# EVK-NORA-W4_SCHEM_0003_USBhub_FTDI.net
KiCad netlist of a schematic drawn in Altium Designer
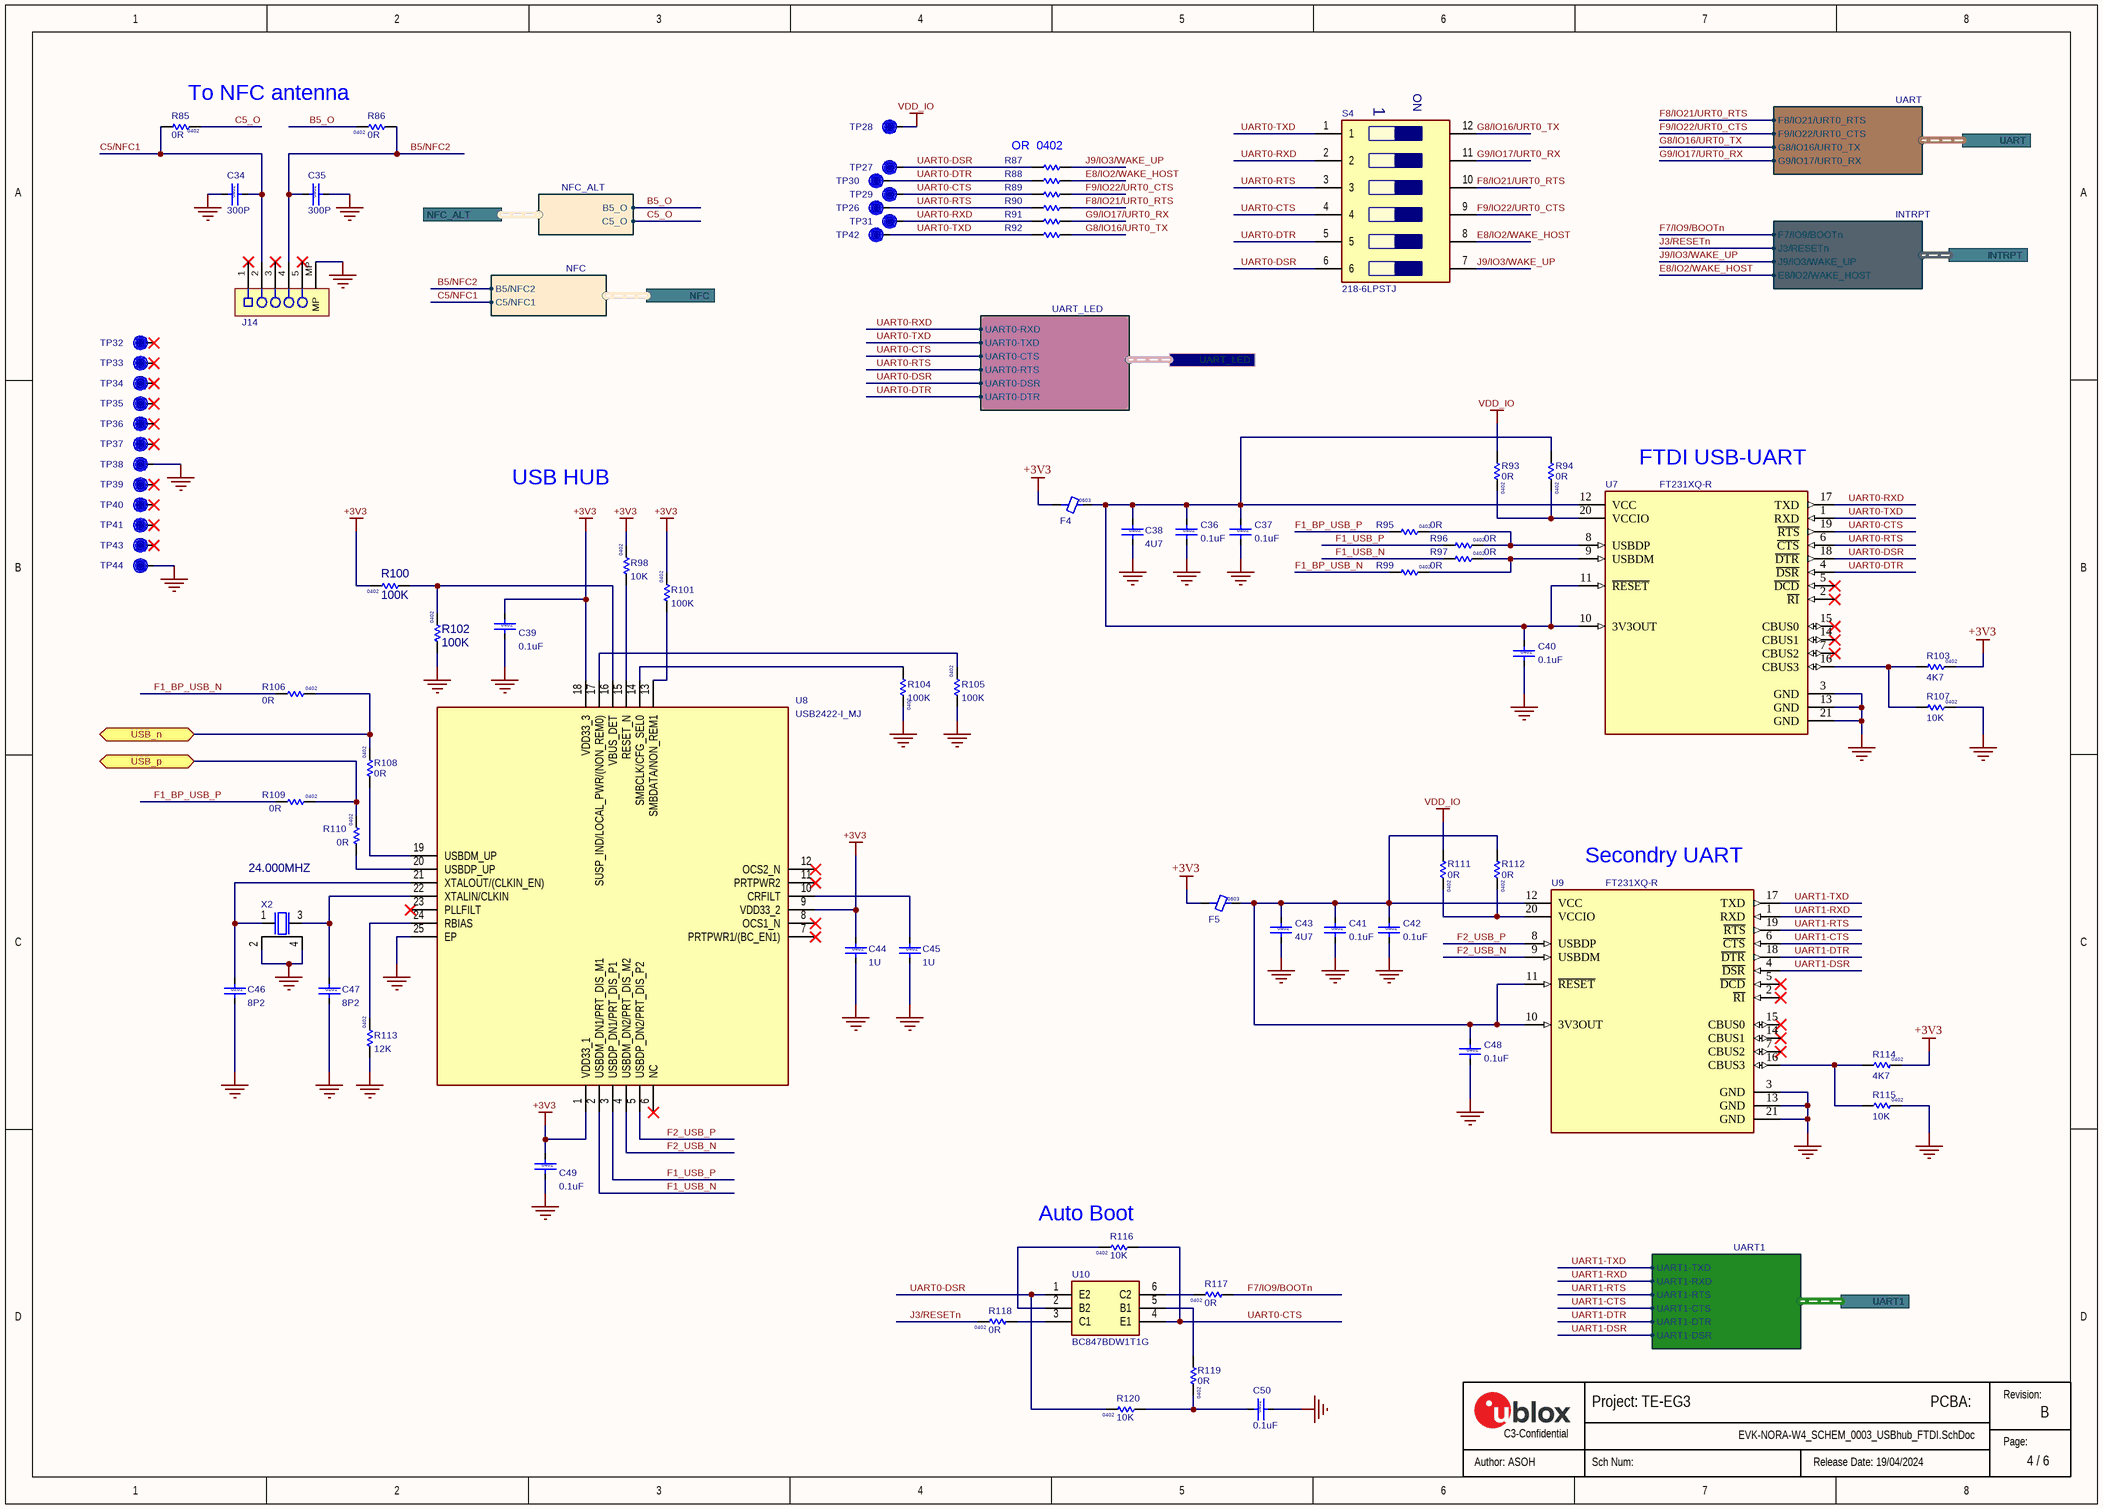
[diagram p0: EVK-NORA-W4_SCHEM_0003_USBhub_FTDI.SchDoc]

(export (version "E")
  (design (tool "Eeschema 10.0.6"))
  (components
    (comp (ref "C34")
      (value "300P")
      (footprint "Cap 0402 HD")
      (description "CAP CER C0G 0402 300P 50V")
      (fields
        (field (name "SIZE") "0402")
        (field (name "PART NUMBER") "UBXH01-0000594")
        (field (name "MANUFACTURER") "Murata Manufacturing Company, Ltd.")
        (field (name "EDITOR") "eric.moog")
      )
      (libsource (lib "UBX_Parts_DB_Lib") (part "Cap Chip"))
    )
    (comp (ref "C35")
      (value "300P")
      (footprint "Cap 0402 HD")
      (description "CAP CER C0G 0402 300P 50V")
      (fields
        (field (name "SIZE") "0402")
        (field (name "PART NUMBER") "UBXH01-0000594")
        (field (name "MANUFACTURER") "Murata Manufacturing Company, Ltd.")
        (field (name "EDITOR") "eric.moog")
      )
      (libsource (lib "UBX_Parts_DB_Lib") (part "Cap Chip"))
    )
    (comp (ref "C36")
      (value "0.1uF")
      (footprint "Cap 0402 HD")
      (description "Cap, Ceramic 0.1uF 10V 10% X5R 0402")
      (fields
        (field (name "SIZE") "0402")
        (field (name "PART NUMBER") "120-00016")
        (field (name "MANUFACTURER") "Murata Electronics North America")
      )
      (libsource (lib "Arena_Parts_DB_Lib") (part "Cap Chip"))
    )
    (comp (ref "C37")
      (value "0.1uF")
      (footprint "Cap 0402 HD")
      (description "Cap, Ceramic 0.1uF 10V 10% X5R 0402")
      (fields
        (field (name "SIZE") "0402")
        (field (name "PART NUMBER") "120-00016")
        (field (name "MANUFACTURER") "Murata Electronics North America")
      )
      (libsource (lib "Arena_Parts_DB_Lib") (part "Cap Chip"))
    )
    (comp (ref "C38")
      (value "4U7")
      (footprint "Cap 0402 HD")
      (description "CAP CER X5R 0402 4U7 20% 10V")
      (fields
        (field (name "SIZE") "0402")
        (field (name "PART NUMBER") "UBXH01-0000243")
        (field (name "TOLERANCE") "20%")
        (field (name "EDITOR") "martin.pilik")
        (field (name "RELEASED BY") "fabrice.bret-dibat")
      )
      (libsource (lib "UBX_Parts_DB_Lib") (part "Cap Chip"))
    )
    (comp (ref "C39")
      (value "0.1uF")
      (footprint "Cap 0402 HD")
      (description "Cap, Ceramic 0.1uF 10V 10% X5R 0402")
      (fields
        (field (name "SIZE") "0402")
        (field (name "PART NUMBER") "120-00016")
        (field (name "MANUFACTURER") "Murata Electronics North America")
      )
      (libsource (lib "Arena_Parts_DB_Lib") (part "Cap Chip"))
    )
    (comp (ref "C40")
      (value "0.1uF")
      (footprint "Cap 0402 HD")
      (description "Cap, Ceramic 0.1uF 10V 10% X5R 0402")
      (fields
        (field (name "SIZE") "0402")
        (field (name "PART NUMBER") "120-00016")
        (field (name "MANUFACTURER") "Murata Electronics North America")
      )
      (libsource (lib "Arena_Parts_DB_Lib") (part "Cap Chip"))
    )
    (comp (ref "C41")
      (value "0.1uF")
      (footprint "Cap 0402 HD")
      (description "Cap, Ceramic 0.1uF 10V 10% X5R 0402")
      (fields
        (field (name "SIZE") "0402")
        (field (name "PART NUMBER") "120-00016")
        (field (name "MANUFACTURER") "Murata Electronics North America")
      )
      (libsource (lib "Arena_Parts_DB_Lib") (part "Cap Chip"))
    )
    (comp (ref "C42")
      (value "0.1uF")
      (footprint "Cap 0402 HD")
      (description "Cap, Ceramic 0.1uF 10V 10% X5R 0402")
      (fields
        (field (name "SIZE") "0402")
        (field (name "PART NUMBER") "120-00016")
        (field (name "MANUFACTURER") "Murata Electronics North America")
      )
      (libsource (lib "Arena_Parts_DB_Lib") (part "Cap Chip"))
    )
    (comp (ref "C43")
      (value "4U7")
      (footprint "Cap 0402 HD")
      (description "CAP CER X5R 0402 4U7 20% 10V")
      (fields
        (field (name "SIZE") "0402")
        (field (name "PART NUMBER") "UBXH01-0000243")
        (field (name "TOLERANCE") "20%")
        (field (name "EDITOR") "martin.pilik")
        (field (name "RELEASED BY") "fabrice.bret-dibat")
      )
      (libsource (lib "UBX_Parts_DB_Lib") (part "Cap Chip"))
    )
    (comp (ref "C44")
      (value "1U")
      (footprint "Cap 0402 HD")
      (description "CAP CER X5R 0402 1U 10% 10V")
      (fields
        (field (name "SIZE") "0402")
        (field (name "PART NUMBER") "UBXH01-0000248")
        (field (name "TOLERANCE") "10%")
        (field (name "EDITOR") "michael.hein")
        (field (name "RELEASED BY") "igor.shevchenko")
      )
      (libsource (lib "UBX_Parts_DB_Lib") (part "Cap Chip"))
    )
    (comp (ref "C45")
      (value "1U")
      (footprint "Cap 0402 HD")
      (description "CAP CER X5R 0402 1U 10% 10V")
      (fields
        (field (name "SIZE") "0402")
        (field (name "PART NUMBER") "UBXH01-0000248")
        (field (name "TOLERANCE") "10%")
        (field (name "EDITOR") "michael.hein")
        (field (name "RELEASED BY") "igor.shevchenko")
      )
      (libsource (lib "UBX_Parts_DB_Lib") (part "Cap Chip"))
    )
    (comp (ref "C46")
      (value "8P2")
      (footprint "Cap 0201 HD")
      (description "CAP CER C0G 0201 8P2 +/-0.5P 25V")
      (fields
        (field (name "SIZE") "0201")
        (field (name "PART NUMBER") "UBXH01-0013002")
        (field (name "TOLERANCE") "+/-0.5P")
        (field (name "EDITOR") "roland.rust")
        (field (name "RELEASED BY") "roland.rust")
      )
      (libsource (lib "UBX_Parts_DB_Lib") (part "Cap Chip"))
    )
    (comp (ref "C47")
      (value "8P2")
      (footprint "Cap 0201 HD")
      (description "CAP CER C0G 0201 8P2 +/-0.5P 25V")
      (fields
        (field (name "SIZE") "0201")
        (field (name "PART NUMBER") "UBXH01-0013002")
        (field (name "TOLERANCE") "+/-0.5P")
        (field (name "EDITOR") "roland.rust")
        (field (name "RELEASED BY") "roland.rust")
      )
      (libsource (lib "UBX_Parts_DB_Lib") (part "Cap Chip"))
    )
    (comp (ref "C48")
      (value "0.1uF")
      (footprint "Cap 0402 HD")
      (description "Cap, Ceramic 0.1uF 10V 10% X5R 0402")
      (fields
        (field (name "SIZE") "0402")
        (field (name "PART NUMBER") "120-00016")
        (field (name "MANUFACTURER") "Murata Electronics North America")
      )
      (libsource (lib "Arena_Parts_DB_Lib") (part "Cap Chip"))
    )
    (comp (ref "C49")
      (value "0.1uF")
      (footprint "Cap 0402 HD")
      (description "Cap, Ceramic 0.1uF 10V 10% X5R 0402")
      (fields
        (field (name "SIZE") "0402")
        (field (name "PART NUMBER") "120-00016")
        (field (name "MANUFACTURER") "Murata Electronics North America")
      )
      (libsource (lib "Arena_Parts_DB_Lib") (part "Cap Chip"))
    )
    (comp (ref "C50")
      (value "0.1uF")
      (footprint "Cap 0402 HD")
      (description "Cap, Ceramic 0.1uF 10V 10% X5R 0402")
      (fields
        (field (name "SIZE") "0402")
        (field (name "PART NUMBER") "120-00016")
        (field (name "MANUFACTURER") "Murata Electronics North America")
      )
      (libsource (lib "Arena_Parts_DB_Lib") (part "Cap Chip"))
    )
    (comp (ref "F4")
      (value "UBXH08-0000001")
      (footprint "IND_0603_1750Lx950Wx1050H_600x800Pad_800G_FLX")
      (description "FERRITE BEAD 0603 600 OHM AT 100MHZ 600OHM 500mA")
      (fields
        (field (name "SIZE") "0603")
        (field (name "MANUFACTURER") "TDK Corporation")
        (field (name "EDITOR") "daniel.hurni")
        (field (name "RELEASED BY") "martin.frauchiger")
      )
      (libsource (lib "UBX_Parts_DB_Lib") (part "FB sm"))
    )
    (comp (ref "F5")
      (value "UBXH08-0000001")
      (footprint "IND_0603_1750Lx950Wx1050H_600x800Pad_800G_FLX")
      (description "FERRITE BEAD 0603 600 OHM AT 100MHZ 600OHM 500mA")
      (fields
        (field (name "SIZE") "0603")
        (field (name "MANUFACTURER") "TDK Corporation")
        (field (name "EDITOR") "daniel.hurni")
        (field (name "RELEASED BY") "martin.frauchiger")
      )
      (libsource (lib "UBX_Parts_DB_Lib") (part "FB sm"))
    )
    (comp (ref "J14")
      (value "UBXH04-0000798")
      (footprint "AVX/Kyocera - 046284005001846")
      (description "0.50MM PITCH SMD RA FFC FPC CONN 5 -PIN 50V 400mA")
      (fields
        (field (name "VOLTAGE") "50V")
        (field (name "MANUFACTURER") "AVX")
        (field (name "EDITOR") "eric.moog")
      )
      (libsource (lib "UBX_Parts_DB_Lib") (part "CON-5Pin_1Row-046284005001846"))
    )
    (comp (ref "R85")
      (value "0R")
      (footprint "RES 0402 HD")
      (description "RES THICK FILM CHIP 0402 0R 0 100mW")
      (fields
        (field (name "SIZE") "0402")
        (field (name "PART NUMBER") "UBXH18-0003002")
        (field (name "TOLERANCE") "0")
        (field (name "EDITOR") "charlotte.biber")
        (field (name "RELEASED BY") "peter.mueller")
      )
      (libsource (lib "UBX_Parts_DB_Lib") (part "Res sm"))
    )
    (comp (ref "R86")
      (value "0R")
      (footprint "RES 0402 HD")
      (description "RES THICK FILM CHIP 0402 0R 0 100mW")
      (fields
        (field (name "SIZE") "0402")
        (field (name "PART NUMBER") "UBXH18-0003002")
        (field (name "TOLERANCE") "0")
        (field (name "EDITOR") "charlotte.biber")
        (field (name "RELEASED BY") "peter.mueller")
      )
      (libsource (lib "UBX_Parts_DB_Lib") (part "Res sm"))
    )
    (comp (ref "R87")
      (value "UBXH18-00030020R")
      (footprint "RES 0402 HD")
      (description "RES THICK FILM CHIP 0402 0R 0 100mW")
      (fields
        (field (name "PART NUMBER") "UBXH18-0003002")
        (field (name "TOLERANCE") "0")
        (field (name "EDITOR") "charlotte.biber")
        (field (name "RELEASED BY") "peter.mueller")
      )
      (libsource (lib "UBX_Parts_DB_Lib") (part "Res sm"))
    )
    (comp (ref "R88")
      (value "UBXH18-00030020R")
      (footprint "RES 0402 HD")
      (description "RES THICK FILM CHIP 0402 0R 0 100mW")
      (fields
        (field (name "PART NUMBER") "UBXH18-0003002")
        (field (name "TOLERANCE") "0")
        (field (name "EDITOR") "charlotte.biber")
        (field (name "RELEASED BY") "peter.mueller")
      )
      (libsource (lib "UBX_Parts_DB_Lib") (part "Res sm"))
    )
    (comp (ref "R89")
      (value "UBXH18-00030020R")
      (footprint "RES 0402 HD")
      (description "RES THICK FILM CHIP 0402 0R 0 100mW")
      (fields
        (field (name "PART NUMBER") "UBXH18-0003002")
        (field (name "TOLERANCE") "0")
        (field (name "EDITOR") "charlotte.biber")
        (field (name "RELEASED BY") "peter.mueller")
      )
      (libsource (lib "UBX_Parts_DB_Lib") (part "Res sm"))
    )
    (comp (ref "R90")
      (value "UBXH18-00030020R")
      (footprint "RES 0402 HD")
      (description "RES THICK FILM CHIP 0402 0R 0 100mW")
      (fields
        (field (name "PART NUMBER") "UBXH18-0003002")
        (field (name "TOLERANCE") "0")
        (field (name "EDITOR") "charlotte.biber")
        (field (name "RELEASED BY") "peter.mueller")
      )
      (libsource (lib "UBX_Parts_DB_Lib") (part "Res sm"))
    )
    (comp (ref "R91")
      (value "UBXH18-00030020R")
      (footprint "RES 0402 HD")
      (description "RES THICK FILM CHIP 0402 0R 0 100mW")
      (fields
        (field (name "PART NUMBER") "UBXH18-0003002")
        (field (name "TOLERANCE") "0")
        (field (name "EDITOR") "charlotte.biber")
        (field (name "RELEASED BY") "peter.mueller")
      )
      (libsource (lib "UBX_Parts_DB_Lib") (part "Res sm"))
    )
    (comp (ref "R92")
      (value "UBXH18-00030020R")
      (footprint "RES 0402 HD")
      (description "RES THICK FILM CHIP 0402 0R 0 100mW")
      (fields
        (field (name "PART NUMBER") "UBXH18-0003002")
        (field (name "TOLERANCE") "0")
        (field (name "EDITOR") "charlotte.biber")
        (field (name "RELEASED BY") "peter.mueller")
      )
      (libsource (lib "UBX_Parts_DB_Lib") (part "Res sm"))
    )
    (comp (ref "R93")
      (value "0R")
      (footprint "RES 0402 HD")
      (description "RES THICK FILM CHIP 0402 0R 0 100mW")
      (fields
        (field (name "SIZE") "0402")
        (field (name "PART NUMBER") "UBXH18-0003002")
        (field (name "TOLERANCE") "0")
        (field (name "EDITOR") "charlotte.biber")
        (field (name "RELEASED BY") "peter.mueller")
      )
      (libsource (lib "UBX_Parts_DB_Lib") (part "Res sm"))
    )
    (comp (ref "R94")
      (value "0R")
      (footprint "RES 0402 HD")
      (description "RES THICK FILM CHIP 0402 0R 0 100mW")
      (fields
        (field (name "SIZE") "0402")
        (field (name "PART NUMBER") "UBXH18-0003002")
        (field (name "TOLERANCE") "0")
        (field (name "EDITOR") "charlotte.biber")
        (field (name "RELEASED BY") "peter.mueller")
      )
      (libsource (lib "UBX_Parts_DB_Lib") (part "Res sm"))
    )
    (comp (ref "R95")
      (value "0R")
      (footprint "RES 0402 HD")
      (description "RES THICK FILM CHIP 0402 0R 0 100mW")
      (fields
        (field (name "SIZE") "0402")
        (field (name "PART NUMBER") "UBXH18-0003002")
        (field (name "TOLERANCE") "0")
        (field (name "EDITOR") "charlotte.biber")
        (field (name "RELEASED BY") "peter.mueller")
      )
      (libsource (lib "UBX_Parts_DB_Lib") (part "Res sm"))
    )
    (comp (ref "R96")
      (value "0R")
      (footprint "RES 0402 HD")
      (description "RES THICK FILM CHIP 0402 0R 0 100mW")
      (fields
        (field (name "SIZE") "0402")
        (field (name "PART NUMBER") "UBXH18-0003002")
        (field (name "TOLERANCE") "0")
        (field (name "EDITOR") "charlotte.biber")
        (field (name "RELEASED BY") "peter.mueller")
      )
      (libsource (lib "UBX_Parts_DB_Lib") (part "Res sm"))
    )
    (comp (ref "R97")
      (value "0R")
      (footprint "RES 0402 HD")
      (description "RES THICK FILM CHIP 0402 0R 0 100mW")
      (fields
        (field (name "SIZE") "0402")
        (field (name "PART NUMBER") "UBXH18-0003002")
        (field (name "TOLERANCE") "0")
        (field (name "EDITOR") "charlotte.biber")
        (field (name "RELEASED BY") "peter.mueller")
      )
      (libsource (lib "UBX_Parts_DB_Lib") (part "Res sm"))
    )
    (comp (ref "R98")
      (value "10K")
      (footprint "RES 0402 HD")
      (description "RES THICK FILM CHIP 0402 10K 1% 63mW")
      (fields
        (field (name "SIZE") "0402")
        (field (name "PART NUMBER") "UBXH18-0000065")
        (field (name "TOLERANCE") "1%")
        (field (name "EDITOR") "erian.bezhani")
        (field (name "RELEASED BY") "massimo.vlacci")
      )
      (libsource (lib "UBX_Parts_DB_Lib") (part "Res sm"))
    )
    (comp (ref "R99")
      (value "0R")
      (footprint "RES 0402 HD")
      (description "RES THICK FILM CHIP 0402 0R 0 100mW")
      (fields
        (field (name "SIZE") "0402")
        (field (name "PART NUMBER") "UBXH18-0003002")
        (field (name "TOLERANCE") "0")
        (field (name "EDITOR") "charlotte.biber")
        (field (name "RELEASED BY") "peter.mueller")
      )
      (libsource (lib "UBX_Parts_DB_Lib") (part "Res sm"))
    )
    (comp (ref "R100")
      (value "100K")
      (footprint "RES 0402 HD")
      (description "RES THICK FILM CHIP 0402 100K 1% 63mW")
      (fields
        (field (name "SIZE") "0402")
        (field (name "PART NUMBER") "UBXH18-0000005")
        (field (name "TOLERANCE") "1%")
        (field (name "EDITOR") "dario.antonaz")
        (field (name "RELEASED BY") "sandro.sestan")
      )
      (libsource (lib "UBX_Parts_DB_Lib") (part "Res sm"))
    )
    (comp (ref "R101")
      (value "100K")
      (footprint "RES 0402 HD")
      (description "RES THICK FILM CHIP 0402 100K 1% 63mW")
      (fields
        (field (name "SIZE") "0402")
        (field (name "PART NUMBER") "UBXH18-0000005")
        (field (name "TOLERANCE") "1%")
        (field (name "EDITOR") "dario.antonaz")
        (field (name "RELEASED BY") "sandro.sestan")
      )
      (libsource (lib "UBX_Parts_DB_Lib") (part "Res sm"))
    )
    (comp (ref "R102")
      (value "100K")
      (footprint "RES 0402 HD")
      (description "RES THICK FILM CHIP 0402 100K 1% 63mW")
      (fields
        (field (name "SIZE") "0402")
        (field (name "PART NUMBER") "UBXH18-0000005")
        (field (name "TOLERANCE") "1%")
        (field (name "EDITOR") "dario.antonaz")
        (field (name "RELEASED BY") "sandro.sestan")
      )
      (libsource (lib "UBX_Parts_DB_Lib") (part "Res sm"))
    )
    (comp (ref "R103")
      (value "4K7")
      (footprint "RES_0402_1100Lx600Wx400H_500x600Pad_400G_FLX")
      (description "RES THICK FILM CHIP 0402 4K7 5% 100mW")
      (fields
        (field (name "SIZE") "0402")
        (field (name "PART NUMBER") "UBXH18-0008065")
        (field (name "TOLERANCE") "5%")
        (field (name "EDITOR") "martin.frauchiger")
        (field (name "RELEASED BY") "martin.frauchiger")
      )
      (libsource (lib "UBX_Parts_DB_Lib") (part "Res sm"))
    )
    (comp (ref "R104")
      (value "100K")
      (footprint "RES 0402 HD")
      (description "RES THICK FILM CHIP 0402 100K 1% 63mW")
      (fields
        (field (name "SIZE") "0402")
        (field (name "PART NUMBER") "UBXH18-0000005")
        (field (name "TOLERANCE") "1%")
        (field (name "EDITOR") "dario.antonaz")
        (field (name "RELEASED BY") "sandro.sestan")
      )
      (libsource (lib "UBX_Parts_DB_Lib") (part "Res sm"))
    )
    (comp (ref "R105")
      (value "100K")
      (footprint "RES 0402 HD")
      (description "RES THICK FILM CHIP 0402 100K 1% 63mW")
      (fields
        (field (name "SIZE") "0402")
        (field (name "PART NUMBER") "UBXH18-0000005")
        (field (name "TOLERANCE") "1%")
        (field (name "EDITOR") "dario.antonaz")
        (field (name "RELEASED BY") "sandro.sestan")
      )
      (libsource (lib "UBX_Parts_DB_Lib") (part "Res sm"))
    )
    (comp (ref "R106")
      (value "0R")
      (footprint "RES 0402 HD")
      (description "RES THICK FILM CHIP 0402 0R 0 100mW")
      (fields
        (field (name "SIZE") "0402")
        (field (name "PART NUMBER") "UBXH18-0003002")
        (field (name "TOLERANCE") "0")
        (field (name "EDITOR") "charlotte.biber")
        (field (name "RELEASED BY") "peter.mueller")
      )
      (libsource (lib "UBX_Parts_DB_Lib") (part "Res sm"))
    )
    (comp (ref "R107")
      (value "10K")
      (footprint "RES_0402_1100Lx600Wx400H_500x600Pad_400G_FLX")
      (description "RES THICK FILM CHIP 0402 10K 5% 100mW")
      (fields
        (field (name "SIZE") "0402")
        (field (name "PART NUMBER") "UBXH18-0008073")
        (field (name "TOLERANCE") "5%")
        (field (name "EDITOR") "martin.frauchiger")
        (field (name "RELEASED BY") "martin.frauchiger")
      )
      (libsource (lib "UBX_Parts_DB_Lib") (part "Res sm"))
    )
    (comp (ref "R108")
      (value "0R")
      (footprint "RES 0402 HD")
      (description "RES THICK FILM CHIP 0402 0R 0 100mW")
      (fields
        (field (name "SIZE") "0402")
        (field (name "PART NUMBER") "UBXH18-0003002")
        (field (name "TOLERANCE") "0")
        (field (name "EDITOR") "charlotte.biber")
        (field (name "RELEASED BY") "peter.mueller")
      )
      (libsource (lib "UBX_Parts_DB_Lib") (part "Res sm"))
    )
    (comp (ref "R109")
      (value "0R")
      (footprint "RES 0402 HD")
      (description "RES THICK FILM CHIP 0402 0R 0 100mW")
      (fields
        (field (name "SIZE") "0402")
        (field (name "PART NUMBER") "UBXH18-0003002")
        (field (name "TOLERANCE") "0")
        (field (name "EDITOR") "charlotte.biber")
        (field (name "RELEASED BY") "peter.mueller")
      )
      (libsource (lib "UBX_Parts_DB_Lib") (part "Res sm"))
    )
    (comp (ref "R110")
      (value "0R")
      (footprint "RES 0402 HD")
      (description "RES THICK FILM CHIP 0402 0R 0 100mW")
      (fields
        (field (name "SIZE") "0402")
        (field (name "PART NUMBER") "UBXH18-0003002")
        (field (name "TOLERANCE") "0")
        (field (name "EDITOR") "charlotte.biber")
        (field (name "RELEASED BY") "peter.mueller")
      )
      (libsource (lib "UBX_Parts_DB_Lib") (part "Res sm"))
    )
    (comp (ref "R111")
      (value "0R")
      (footprint "RES 0402 HD")
      (description "RES THICK FILM CHIP 0402 0R 0 100mW")
      (fields
        (field (name "SIZE") "0402")
        (field (name "PART NUMBER") "UBXH18-0003002")
        (field (name "TOLERANCE") "0")
        (field (name "EDITOR") "charlotte.biber")
        (field (name "RELEASED BY") "peter.mueller")
      )
      (libsource (lib "UBX_Parts_DB_Lib") (part "Res sm"))
    )
    (comp (ref "R112")
      (value "0R")
      (footprint "RES 0402 HD")
      (description "RES THICK FILM CHIP 0402 0R 0 100mW")
      (fields
        (field (name "SIZE") "0402")
        (field (name "PART NUMBER") "UBXH18-0003002")
        (field (name "TOLERANCE") "0")
        (field (name "EDITOR") "charlotte.biber")
        (field (name "RELEASED BY") "peter.mueller")
      )
      (libsource (lib "UBX_Parts_DB_Lib") (part "Res sm"))
    )
    (comp (ref "R113")
      (value "12K")
      (footprint "RES_0402_1100Lx600Wx400H_500x600Pad_400G_FLX")
      (description "RES THICK FILM CHIP 0402 12K 1% 62.5mW")
      (fields
        (field (name "SIZE") "0402")
        (field (name "PART NUMBER") "UBXH18-0000133")
        (field (name "TOLERANCE") "1%")
        (field (name "EDITOR") "pierpaolo.arban")
        (field (name "RELEASED BY") "dario.antonaz")
      )
      (libsource (lib "UBX_Parts_DB_Lib") (part "Res sm"))
    )
    (comp (ref "R114")
      (value "4K7")
      (footprint "RES_0402_1100Lx600Wx400H_500x600Pad_400G_FLX")
      (description "RES THICK FILM CHIP 0402 4K7 5% 100mW")
      (fields
        (field (name "SIZE") "0402")
        (field (name "PART NUMBER") "UBXH18-0008065")
        (field (name "TOLERANCE") "5%")
        (field (name "EDITOR") "martin.frauchiger")
        (field (name "RELEASED BY") "martin.frauchiger")
      )
      (libsource (lib "UBX_Parts_DB_Lib") (part "Res sm"))
    )
    (comp (ref "R115")
      (value "10K")
      (footprint "RES_0402_1100Lx600Wx400H_500x600Pad_400G_FLX")
      (description "RES THICK FILM CHIP 0402 10K 5% 100mW")
      (fields
        (field (name "SIZE") "0402")
        (field (name "PART NUMBER") "UBXH18-0008073")
        (field (name "TOLERANCE") "5%")
        (field (name "EDITOR") "martin.frauchiger")
        (field (name "RELEASED BY") "martin.frauchiger")
      )
      (libsource (lib "UBX_Parts_DB_Lib") (part "Res sm"))
    )
    (comp (ref "R116")
      (value "10K")
      (footprint "RES 0402 HD")
      (description "RES THICK FILM CHIP 0402 10K 1% 63mW")
      (fields
        (field (name "SIZE") "0402")
        (field (name "PART NUMBER") "UBXH18-0000065")
        (field (name "TOLERANCE") "1%")
        (field (name "EDITOR") "erian.bezhani")
        (field (name "RELEASED BY") "massimo.vlacci")
      )
      (libsource (lib "UBX_Parts_DB_Lib") (part "Res sm"))
    )
    (comp (ref "R117")
      (value "0R")
      (footprint "RES 0402 HD")
      (description "RES THICK FILM CHIP 0402 0R 0 100mW")
      (fields
        (field (name "SIZE") "0402")
        (field (name "PART NUMBER") "UBXH18-0003002")
        (field (name "TOLERANCE") "0")
        (field (name "EDITOR") "charlotte.biber")
        (field (name "RELEASED BY") "peter.mueller")
      )
      (libsource (lib "UBX_Parts_DB_Lib") (part "Res sm"))
    )
    (comp (ref "R118")
      (value "0R")
      (footprint "RES 0402 HD")
      (description "RES THICK FILM CHIP 0402 0R 0 100mW")
      (fields
        (field (name "SIZE") "0402")
        (field (name "PART NUMBER") "UBXH18-0003002")
        (field (name "TOLERANCE") "0")
        (field (name "EDITOR") "charlotte.biber")
        (field (name "RELEASED BY") "peter.mueller")
      )
      (libsource (lib "UBX_Parts_DB_Lib") (part "Res sm"))
    )
    (comp (ref "R119")
      (value "0R")
      (footprint "RES 0402 HD")
      (description "RES THICK FILM CHIP 0402 0R 0 100mW")
      (fields
        (field (name "SIZE") "0402")
        (field (name "PART NUMBER") "UBXH18-0003002")
        (field (name "TOLERANCE") "0")
        (field (name "EDITOR") "charlotte.biber")
        (field (name "RELEASED BY") "peter.mueller")
      )
      (libsource (lib "UBX_Parts_DB_Lib") (part "Res sm"))
    )
    (comp (ref "R120")
      (value "10K")
      (footprint "RES 0402 HD")
      (description "RES THICK FILM CHIP 0402 10K 1% 63mW")
      (fields
        (field (name "SIZE") "0402")
        (field (name "PART NUMBER") "UBXH18-0000065")
        (field (name "TOLERANCE") "1%")
        (field (name "EDITOR") "erian.bezhani")
        (field (name "RELEASED BY") "massimo.vlacci")
      )
      (libsource (lib "UBX_Parts_DB_Lib") (part "Res sm"))
    )
    (comp (ref "S4")
      (value "218-6LPSTJ")
      (footprint "SamacSys:2186LPSTJ")
      (description "Switch")
      (fields (field (name "MOUSER PART NUMBER") "774-2186LPSTJ"))
      (libsource (lib "SamacSys") (part "218-6LPSTJ"))
    )
    (comp (ref "TP26")
      (value "TP")
      (footprint "TP10R")
      (description "Testpoint, Round 1.0mm Dia")
      (fields
        (field (name "PART NUMBER") "TP10R")
        (field (name "ADDED BY") "Jeremy D")
        (field (name "CHECKED BY") "Paul B")
      )
      (libsource (lib "LEGACY_Rigado_AltiumLib") (part "TP_R"))
    )
    (comp (ref "TP27")
      (value "TP")
      (footprint "TP10R")
      (description "Testpoint, Round 1.0mm Dia")
      (fields
        (field (name "PART NUMBER") "TP10R")
        (field (name "ADDED BY") "Jeremy D")
        (field (name "CHECKED BY") "Paul B")
      )
      (libsource (lib "LEGACY_Rigado_AltiumLib") (part "TP_R"))
    )
    (comp (ref "TP28")
      (value "TP")
      (footprint "TP10R")
      (description "Testpoint, Round 1.0mm Dia")
      (fields
        (field (name "PART NUMBER") "TP10R")
        (field (name "ADDED BY") "Jeremy D")
        (field (name "CHECKED BY") "Paul B")
      )
      (libsource (lib "LEGACY_Rigado_AltiumLib") (part "TP_R"))
    )
    (comp (ref "TP29")
      (value "TP")
      (footprint "TP10R")
      (description "Testpoint, Round 1.0mm Dia")
      (fields
        (field (name "PART NUMBER") "TP10R")
        (field (name "ADDED BY") "Jeremy D")
        (field (name "CHECKED BY") "Paul B")
      )
      (libsource (lib "LEGACY_Rigado_AltiumLib") (part "TP_R"))
    )
    (comp (ref "TP30")
      (value "TP")
      (footprint "TP10R")
      (description "Testpoint, Round 1.0mm Dia")
      (fields
        (field (name "PART NUMBER") "TP10R")
        (field (name "ADDED BY") "Jeremy D")
        (field (name "CHECKED BY") "Paul B")
      )
      (libsource (lib "LEGACY_Rigado_AltiumLib") (part "TP_R"))
    )
    (comp (ref "TP31")
      (value "TP")
      (footprint "TP10R")
      (description "Testpoint, Round 1.0mm Dia")
      (fields
        (field (name "PART NUMBER") "TP10R")
        (field (name "ADDED BY") "Jeremy D")
        (field (name "CHECKED BY") "Paul B")
      )
      (libsource (lib "LEGACY_Rigado_AltiumLib") (part "TP_R"))
    )
    (comp (ref "TP32")
      (value "TP")
      (footprint "TP10R")
      (description "Testpoint, Round 1.0mm Dia")
      (fields
        (field (name "PART NUMBER") "TP10R")
        (field (name "ADDED BY") "Jeremy D")
        (field (name "CHECKED BY") "Paul B")
      )
      (libsource (lib "LEGACY_Rigado_AltiumLib") (part "TP_R"))
    )
    (comp (ref "TP33")
      (value "TP")
      (footprint "TP10R")
      (description "Testpoint, Round 1.0mm Dia")
      (fields
        (field (name "PART NUMBER") "TP10R")
        (field (name "ADDED BY") "Jeremy D")
        (field (name "CHECKED BY") "Paul B")
      )
      (libsource (lib "LEGACY_Rigado_AltiumLib") (part "TP_R"))
    )
    (comp (ref "TP34")
      (value "TP")
      (footprint "TP10R")
      (description "Testpoint, Round 1.0mm Dia")
      (fields
        (field (name "PART NUMBER") "TP10R")
        (field (name "ADDED BY") "Jeremy D")
        (field (name "CHECKED BY") "Paul B")
      )
      (libsource (lib "LEGACY_Rigado_AltiumLib") (part "TP_R"))
    )
    (comp (ref "TP35")
      (value "TP")
      (footprint "TP10R")
      (description "Testpoint, Round 1.0mm Dia")
      (fields
        (field (name "PART NUMBER") "TP10R")
        (field (name "ADDED BY") "Jeremy D")
        (field (name "CHECKED BY") "Paul B")
      )
      (libsource (lib "LEGACY_Rigado_AltiumLib") (part "TP_R"))
    )
    (comp (ref "TP36")
      (value "TP")
      (footprint "TP10R")
      (description "Testpoint, Round 1.0mm Dia")
      (fields
        (field (name "PART NUMBER") "TP10R")
        (field (name "ADDED BY") "Jeremy D")
        (field (name "CHECKED BY") "Paul B")
      )
      (libsource (lib "LEGACY_Rigado_AltiumLib") (part "TP_R"))
    )
    (comp (ref "TP37")
      (value "TP")
      (footprint "TP10R")
      (description "Testpoint, Round 1.0mm Dia")
      (fields
        (field (name "PART NUMBER") "TP10R")
        (field (name "ADDED BY") "Jeremy D")
        (field (name "CHECKED BY") "Paul B")
      )
      (libsource (lib "LEGACY_Rigado_AltiumLib") (part "TP_R"))
    )
    (comp (ref "TP38")
      (value "TP")
      (footprint "TP10R")
      (description "Testpoint, Round 1.0mm Dia")
      (fields
        (field (name "PART NUMBER") "TP10R")
        (field (name "ADDED BY") "Jeremy D")
        (field (name "CHECKED BY") "Paul B")
      )
      (libsource (lib "LEGACY_Rigado_AltiumLib") (part "TP_R"))
    )
    (comp (ref "TP39")
      (value "TP")
      (footprint "TP10R")
      (description "Testpoint, Round 1.0mm Dia")
      (fields
        (field (name "PART NUMBER") "TP10R")
        (field (name "ADDED BY") "Jeremy D")
        (field (name "CHECKED BY") "Paul B")
      )
      (libsource (lib "LEGACY_Rigado_AltiumLib") (part "TP_R"))
    )
    (comp (ref "TP40")
      (value "TP")
      (footprint "TP10R")
      (description "Testpoint, Round 1.0mm Dia")
      (fields
        (field (name "PART NUMBER") "TP10R")
        (field (name "ADDED BY") "Jeremy D")
        (field (name "CHECKED BY") "Paul B")
      )
      (libsource (lib "LEGACY_Rigado_AltiumLib") (part "TP_R"))
    )
    (comp (ref "TP41")
      (value "TP")
      (footprint "TP10R")
      (description "Testpoint, Round 1.0mm Dia")
      (fields
        (field (name "PART NUMBER") "TP10R")
        (field (name "ADDED BY") "Jeremy D")
        (field (name "CHECKED BY") "Paul B")
      )
      (libsource (lib "LEGACY_Rigado_AltiumLib") (part "TP_R"))
    )
    (comp (ref "TP42")
      (value "TP")
      (footprint "TP10R")
      (description "Testpoint, Round 1.0mm Dia")
      (fields
        (field (name "PART NUMBER") "TP10R")
        (field (name "ADDED BY") "Jeremy D")
        (field (name "CHECKED BY") "Paul B")
      )
      (libsource (lib "LEGACY_Rigado_AltiumLib") (part "TP_R"))
    )
    (comp (ref "TP43")
      (value "TP")
      (footprint "TP10R")
      (description "Testpoint, Round 1.0mm Dia")
      (fields
        (field (name "PART NUMBER") "TP10R")
        (field (name "ADDED BY") "Jeremy D")
        (field (name "CHECKED BY") "Paul B")
      )
      (libsource (lib "LEGACY_Rigado_AltiumLib") (part "TP_R"))
    )
    (comp (ref "TP44")
      (value "TP")
      (footprint "TP10R")
      (description "Testpoint, Round 1.0mm Dia")
      (fields
        (field (name "PART NUMBER") "TP10R")
        (field (name "ADDED BY") "Jeremy D")
        (field (name "CHECKED BY") "Paul B")
      )
      (libsource (lib "LEGACY_Rigado_AltiumLib") (part "TP_R"))
    )
    (comp (ref "U7")
      (value "FT231XQ-R")
      (footprint "QFN_5x5_FT231XQ")
      (description "FTDI USB TO SERIAL FULL UART INTERFACE QFN20")
      (fields
        (field (name "PART NUMBER") "UBXH10-0000054")
        (field (name "MANUFACTURER") "FTDI Future Technology Devices International")
        (field (name "EDITOR") "adam.johansson")
      )
      (libsource (lib "UBX_Parts_DB_Lib") (part "FT231XQ-R"))
    )
    (comp (ref "U8")
      (value "USB2422-I_MJ")
      (footprint "SamacSys:QFN50P400X400X100-25N-D")
      (description "Integrated Circuit")
      (fields
        (field (name "MANUFACTURER_PART_NUMBER") "USB2422-I/MJ")
        (field (name "MOUSER PART NUMBER") "579-USB2422-I/MJ")
      )
      (libsource (lib "*") (part "USB2422-I_MJ"))
    )
    (comp (ref "U9")
      (value "FT231XQ-R")
      (footprint "QFN_5x5_FT231XQ")
      (description "FTDI USB TO SERIAL FULL UART INTERFACE QFN20")
      (fields
        (field (name "PART NUMBER") "UBXH10-0000054")
        (field (name "MANUFACTURER") "FTDI Future Technology Devices International")
        (field (name "EDITOR") "adam.johansson")
      )
      (libsource (lib "UBX_Parts_DB_Lib") (part "FT231XQ-R"))
    )
    (comp (ref "U10")
      (value "BC847BDW1T1G")
      (footprint "SamacSys:SOT65P210X110-6N")
      (description "Integrated Circuit")
      (fields (field (name "MOUSER PART NUMBER") "863-BC847BDW1T1G"))
      (libsource (lib "*") (part "BC847BDW1T1G"))
    )
    (comp (ref "X2")
      (value "24.000MHZ")
      (footprint "XTAL_2016_HD")
      (description "CRYSTAL CL=8PF EPSON 2.0X1.6MM 24.000MHZ 30PPM")
      (fields
        (field (name "PART NUMBER") "UBXH21-0000066")
        (field (name "TOLERANCE") "30PPM")
        (field (name "EDITOR") "adam.johansson")
        (field (name "RELEASED BY") "olof.viklund")
      )
      (libsource (lib "UBX_Parts_DB_Lib") (part "XTAL_4Pin"))
    )
  )
  (nets
    (net (code "7") (name "+3V3") (class "Default")
      (node (ref "C39") (pin "1") (pinfunction "1_1") (pintype "passive"))
      (node (ref "C44") (pin "1") (pinfunction "1_1") (pintype "passive"))
      (node (ref "C49") (pin "1") (pinfunction "1_1") (pintype "passive"))
      (node (ref "F4") (pin "1") (pinfunction "1_1") (pintype "passive"))
      (node (ref "F5") (pin "1") (pinfunction "1_1") (pintype "passive"))
      (node (ref "R100") (pin "2") (pinfunction "2_2") (pintype "passive"))
      (node (ref "R101") (pin "2") (pinfunction "2_2") (pintype "passive"))
      (node (ref "R103") (pin "2") (pinfunction "2_2") (pintype "passive"))
      (node (ref "R114") (pin "2") (pinfunction "2_2") (pintype "passive"))
      (node (ref "R98") (pin "2") (pinfunction "2_2") (pintype "passive"))
      (node (ref "U8") (pin "1") (pinfunction "VDD33_1_1") (pintype "passive"))
      (node (ref "U8") (pin "18") (pinfunction "VDD33_3_18") (pintype "passive"))
      (node (ref "U8") (pin "9") (pinfunction "VDD33_2_9") (pintype "passive"))
    )
    (net (code "8") (name "/B5_O") (class "Default")
      (node (ref "R86") (pin "2") (pinfunction "2_2") (pintype "passive"))
    )
    (net (code "9") (name "/B5{slash}NFC2") (class "Default")
      (node (ref "C35") (pin "1") (pinfunction "1_1") (pintype "passive"))
      (node (ref "J14") (pin "4") (pinfunction "4_4") (pintype "passive"))
      (node (ref "R86") (pin "1") (pinfunction "1_1") (pintype "passive"))
    )
    (net (code "10") (name "/C5_O") (class "Default")
      (node (ref "R85") (pin "1") (pinfunction "1_1") (pintype "passive"))
    )
    (net (code "11") (name "/C5{slash}NFC1") (class "Default")
      (node (ref "C34") (pin "2") (pinfunction "2_2") (pintype "passive"))
      (node (ref "J14") (pin "2") (pinfunction "2_2") (pintype "passive"))
      (node (ref "R85") (pin "2") (pinfunction "2_2") (pintype "passive"))
    )
    (net (code "12") (name "/E8{slash}IO2{slash}WAKE_HOST") (class "Default")
      (node (ref "R88") (pin "2") (pinfunction "2_2") (pintype "passive"))
      (node (ref "S4") (pin "8") (pintype "passive"))
    )
    (net (code "13") (name "/F1_BP_USB_N") (class "Default")
      (node (ref "R106") (pin "1") (pinfunction "1_1") (pintype "passive"))
      (node (ref "R99") (pin "1") (pinfunction "1_1") (pintype "passive"))
    )
    (net (code "14") (name "/F1_BP_USB_P") (class "Default")
      (node (ref "R109") (pin "1") (pinfunction "1_1") (pintype "passive"))
      (node (ref "R95") (pin "1") (pinfunction "1_1") (pintype "passive"))
    )
    (net (code "15") (name "/F1_USB_N") (class "Default")
      (node (ref "R97") (pin "1") (pinfunction "1_1") (pintype "passive"))
      (node (ref "U8") (pin "2") (pinfunction "USBDM_DN1/PRT_DIS_M1_2") (pintype "passive"))
    )
    (net (code "16") (name "/F1_USB_P") (class "Default")
      (node (ref "R96") (pin "1") (pinfunction "1_1") (pintype "passive"))
      (node (ref "U8") (pin "3") (pinfunction "USBDP_DN1/PRT_DIS_P1_3") (pintype "passive"))
    )
    (net (code "17") (name "/F2_USB_N") (class "Default")
      (node (ref "U8") (pin "4") (pinfunction "USBDM_DN2/PRT_DIS_M2_4") (pintype "passive"))
      (node (ref "U9") (pin "9") (pinfunction "USBDM_9") (pintype "input"))
    )
    (net (code "18") (name "/F2_USB_P") (class "Default")
      (node (ref "U8") (pin "5") (pinfunction "USBDP_DN2/PRT_DIS_P2_5") (pintype "passive"))
      (node (ref "U9") (pin "8") (pinfunction "USBDP_8") (pintype "input"))
    )
    (net (code "19") (name "/F7{slash}IO9{slash}BOOTn") (class "Default")
      (node (ref "R117") (pin "1") (pinfunction "1_1") (pintype "passive"))
    )
    (net (code "20") (name "/F8{slash}IO21{slash}URT0_RTS") (class "Default")
      (node (ref "R90") (pin "2") (pinfunction "2_2") (pintype "passive"))
      (node (ref "S4") (pin "10") (pintype "passive"))
    )
    (net (code "21") (name "/F9{slash}IO22{slash}URT0_CTS") (class "Default")
      (node (ref "R89") (pin "2") (pinfunction "2_2") (pintype "passive"))
      (node (ref "S4") (pin "9") (pintype "passive"))
    )
    (net (code "22") (name "/G8{slash}IO16{slash}URT0_TX") (class "Default")
      (node (ref "R92") (pin "2") (pinfunction "2_2") (pintype "passive"))
      (node (ref "S4") (pin "12") (pintype "passive"))
    )
    (net (code "23") (name "/G9{slash}IO17{slash}URT0_RX") (class "Default")
      (node (ref "R91") (pin "2") (pinfunction "2_2") (pintype "passive"))
      (node (ref "S4") (pin "11") (pintype "passive"))
    )
    (net (code "24") (name "/J3{slash}RESETn") (class "Default")
      (node (ref "R118") (pin "2") (pinfunction "2_2") (pintype "passive"))
    )
    (net (code "25") (name "/J9{slash}IO3{slash}WAKE_UP") (class "Default")
      (node (ref "R87") (pin "2") (pinfunction "2_2") (pintype "passive"))
      (node (ref "S4") (pin "7") (pintype "passive"))
    )
    (net (code "26") (name "/UART0-CTS") (class "Default")
      (node (ref "R116") (pin "1") (pinfunction "1_1") (pintype "passive"))
      (node (ref "R89") (pin "1") (pinfunction "1_1") (pintype "passive"))
      (node (ref "S4") (pin "4") (pinfunction "4_4") (pintype "passive"))
      (node (ref "TP29") (pin "1") (pintype "passive"))
      (node (ref "U10") (pin "4") (pinfunction "E1_4") (pintype "passive"))
      (node (ref "U7") (pin "19") (pinfunction "~{RTS}_19") (pintype "output"))
    )
    (net (code "27") (name "/UART0-DSR") (class "Default")
      (node (ref "R120") (pin "2") (pinfunction "2_2") (pintype "passive"))
      (node (ref "R87") (pin "1") (pinfunction "1_1") (pintype "passive"))
      (node (ref "S4") (pin "6") (pinfunction "6_6") (pintype "passive"))
      (node (ref "TP27") (pin "1") (pintype "passive"))
      (node (ref "U10") (pin "1") (pinfunction "E2_1") (pintype "passive"))
      (node (ref "U7") (pin "18") (pinfunction "~{DTR}_18") (pintype "output"))
    )
    (net (code "28") (name "/UART0-DTR") (class "Default")
      (node (ref "R88") (pin "1") (pinfunction "1_1") (pintype "passive"))
      (node (ref "S4") (pin "5") (pinfunction "5_5") (pintype "passive"))
      (node (ref "TP30") (pin "1") (pintype "passive"))
      (node (ref "U7") (pin "4") (pinfunction "~{DSR}_4") (pintype "input"))
    )
    (net (code "29") (name "/UART0-RTS") (class "Default")
      (node (ref "R90") (pin "1") (pinfunction "1_1") (pintype "passive"))
      (node (ref "S4") (pin "3") (pinfunction "3_3") (pintype "passive"))
      (node (ref "TP26") (pin "1") (pintype "passive"))
      (node (ref "U7") (pin "6") (pinfunction "~{CTS}_6") (pintype "input"))
    )
    (net (code "30") (name "/UART0-RXD") (class "Default")
      (node (ref "R91") (pin "1") (pinfunction "1_1") (pintype "passive"))
      (node (ref "S4") (pin "2") (pinfunction "2_2") (pintype "passive"))
      (node (ref "TP31") (pin "1") (pintype "passive"))
      (node (ref "U7") (pin "17") (pinfunction "TXD_17") (pintype "output"))
    )
    (net (code "31") (name "/UART0-TXD") (class "Default")
      (node (ref "R92") (pin "1") (pinfunction "1_1") (pintype "passive"))
      (node (ref "S4") (pin "1") (pinfunction "1_1") (pintype "passive"))
      (node (ref "TP42") (pin "1") (pintype "passive"))
      (node (ref "U7") (pin "1") (pinfunction "RXD_1") (pintype "input"))
    )
    (net (code "32") (name "/UART1-CTS") (class "Default")
      (node (ref "U9") (pin "6") (pinfunction "~{CTS}_6") (pintype "input"))
    )
    (net (code "33") (name "/UART1-DSR") (class "Default")
      (node (ref "U9") (pin "4") (pinfunction "~{DSR}_4") (pintype "input"))
    )
    (net (code "34") (name "/UART1-DTR") (class "Default")
      (node (ref "U9") (pin "18") (pinfunction "~{DTR}_18") (pintype "output"))
    )
    (net (code "35") (name "/UART1-RTS") (class "Default")
      (node (ref "U9") (pin "19") (pinfunction "~{RTS}_19") (pintype "output"))
    )
    (net (code "36") (name "/UART1-RXD") (class "Default")
      (node (ref "U9") (pin "1") (pinfunction "RXD_1") (pintype "input"))
    )
    (net (code "37") (name "/UART1-TXD") (class "Default")
      (node (ref "U9") (pin "17") (pinfunction "TXD_17") (pintype "output"))
    )
    (net (code "38") (name "/USB_n") (class "Default")
      (node (ref "R106") (pin "2") (pinfunction "2_2") (pintype "passive"))
      (node (ref "R108") (pin "2") (pinfunction "2_2") (pintype "passive"))
    )
    (net (code "39") (name "/USB_p") (class "Default")
      (node (ref "R109") (pin "2") (pinfunction "2_2") (pintype "passive"))
      (node (ref "R110") (pin "2") (pinfunction "2_2") (pintype "passive"))
    )
    (net (code "46") (name "GND") (class "Default")
      (node (ref "C34") (pin "1") (pinfunction "1_1") (pintype "passive"))
      (node (ref "C35") (pin "2") (pinfunction "2_2") (pintype "passive"))
      (node (ref "C36") (pin "2") (pinfunction "2_2") (pintype "passive"))
      (node (ref "C37") (pin "2") (pinfunction "2_2") (pintype "passive"))
      (node (ref "C38") (pin "2") (pinfunction "2_2") (pintype "passive"))
      (node (ref "C39") (pin "2") (pinfunction "2_2") (pintype "passive"))
      (node (ref "C40") (pin "2") (pinfunction "2_2") (pintype "passive"))
      (node (ref "C41") (pin "2") (pinfunction "2_2") (pintype "passive"))
      (node (ref "C42") (pin "2") (pinfunction "2_2") (pintype "passive"))
      (node (ref "C43") (pin "2") (pinfunction "2_2") (pintype "passive"))
      (node (ref "C44") (pin "2") (pinfunction "2_2") (pintype "passive"))
      (node (ref "C45") (pin "2") (pinfunction "2_2") (pintype "passive"))
      (node (ref "C46") (pin "2") (pinfunction "2_2") (pintype "passive"))
      (node (ref "C47") (pin "2") (pinfunction "2_2") (pintype "passive"))
      (node (ref "C48") (pin "2") (pinfunction "2_2") (pintype "passive"))
      (node (ref "C49") (pin "2") (pinfunction "2_2") (pintype "passive"))
      (node (ref "C50") (pin "2") (pinfunction "2_2") (pintype "passive"))
      (node (ref "J14") (pin "MP") (pinfunction "MP_MP") (pintype "passive"))
      (node (ref "R102") (pin "1") (pinfunction "1_1") (pintype "passive"))
      (node (ref "R104") (pin "2") (pinfunction "2_2") (pintype "passive"))
      (node (ref "R105") (pin "1") (pinfunction "1_1") (pintype "passive"))
      (node (ref "R107") (pin "2") (pinfunction "2_2") (pintype "passive"))
      (node (ref "R113") (pin "1") (pinfunction "1_1") (pintype "passive"))
      (node (ref "R115") (pin "2") (pinfunction "2_2") (pintype "passive"))
      (node (ref "TP38") (pin "1") (pintype "passive"))
      (node (ref "TP44") (pin "1") (pintype "passive"))
      (node (ref "U7") (pin "13") (pinfunction "GND_13") (pintype "power_in"))
      (node (ref "U7") (pin "21") (pinfunction "GND_21") (pintype "power_in"))
      (node (ref "U7") (pin "3") (pinfunction "GND_3") (pintype "power_in"))
      (node (ref "U8") (pin "25") (pinfunction "EP_25") (pintype "passive"))
      (node (ref "U9") (pin "13") (pinfunction "GND_13") (pintype "power_in"))
      (node (ref "U9") (pin "21") (pinfunction "GND_21") (pintype "power_in"))
      (node (ref "U9") (pin "3") (pinfunction "GND_3") (pintype "power_in"))
      (node (ref "X2") (pin "2") (pintype "passive"))
      (node (ref "X2") (pin "4") (pintype "passive"))
    )
    (net (code "47") (name "Net-(C50-Pad1)") (class "Default")
      (node (ref "C50") (pin "1") (pinfunction "1_1") (pintype "passive"))
      (node (ref "R119") (pin "2") (pinfunction "2_2") (pintype "passive"))
      (node (ref "R120") (pin "1") (pinfunction "1_1") (pintype "passive"))
    )
    (net (code "48") (name "Net-(U7-3V3OUT)") (class "Default")
      (node (ref "C36") (pin "1") (pinfunction "1_1") (pintype "passive"))
      (node (ref "C37") (pin "1") (pinfunction "1_1") (pintype "passive"))
      (node (ref "C38") (pin "1") (pinfunction "1_1") (pintype "passive"))
      (node (ref "C40") (pin "1") (pinfunction "1_1") (pintype "passive"))
      (node (ref "F4") (pin "2") (pinfunction "2_2") (pintype "passive"))
      (node (ref "R94") (pin "1") (pinfunction "1_1") (pintype "passive"))
      (node (ref "U7") (pin "10") (pinfunction "3V3OUT_10") (pintype "input"))
      (node (ref "U7") (pin "11") (pinfunction "~{RESET}_11") (pintype "input"))
      (node (ref "U7") (pin "12") (pinfunction "VCC_12") (pintype "power_in"))
    )
    (net (code "49") (name "Net-(U7-CBUS3)") (class "Default")
      (node (ref "R103") (pin "1") (pinfunction "1_1") (pintype "passive"))
      (node (ref "R107") (pin "1") (pinfunction "1_1") (pintype "passive"))
      (node (ref "U7") (pin "16") (pinfunction "CBUS3_16") (pintype "bidirectional"))
    )
    (net (code "50") (name "Net-(U7-USBDM)") (class "Default")
      (node (ref "R97") (pin "2") (pinfunction "2_2") (pintype "passive"))
      (node (ref "R99") (pin "2") (pinfunction "2_2") (pintype "passive"))
      (node (ref "U7") (pin "9") (pinfunction "USBDM_9") (pintype "input"))
    )
    (net (code "51") (name "Net-(U7-USBDP)") (class "Default")
      (node (ref "R95") (pin "2") (pinfunction "2_2") (pintype "passive"))
      (node (ref "R96") (pin "2") (pinfunction "2_2") (pintype "passive"))
      (node (ref "U7") (pin "8") (pinfunction "USBDP_8") (pintype "input"))
    )
    (net (code "52") (name "Net-(U7-VCCIO)") (class "Default")
      (node (ref "R93") (pin "2") (pinfunction "2_2") (pintype "passive"))
      (node (ref "R94") (pin "2") (pinfunction "2_2") (pintype "passive"))
      (node (ref "U7") (pin "20") (pinfunction "VCCIO_20") (pintype "power_in"))
    )
    (net (code "53") (name "Net-(U8-CRFILT)") (class "Default")
      (node (ref "C45") (pin "1") (pinfunction "1_1") (pintype "passive"))
      (node (ref "U8") (pin "10") (pinfunction "CRFILT_10") (pintype "passive"))
    )
    (net (code "54") (name "Net-(U8-RBIAS)") (class "Default")
      (node (ref "R113") (pin "2") (pinfunction "2_2") (pintype "passive"))
      (node (ref "U8") (pin "24") (pinfunction "RBIAS_24") (pintype "passive"))
    )
    (net (code "55") (name "Net-(U8-RESET_N)") (class "Default")
      (node (ref "R98") (pin "1") (pinfunction "1_1") (pintype "passive"))
      (node (ref "U8") (pin "15") (pinfunction "RESET_N_15") (pintype "passive"))
    )
    (net (code "56") (name "Net-(U8-SMBCLK{slash}CFG_SEL0)") (class "Default")
      (node (ref "R104") (pin "1") (pinfunction "1_1") (pintype "passive"))
      (node (ref "U8") (pin "14") (pinfunction "SMBCLK/CFG_SEL0_14") (pintype "passive"))
    )
    (net (code "57") (name "Net-(U8-SMBDATA{slash}NON_REM1)") (class "Default")
      (node (ref "R101") (pin "1") (pinfunction "1_1") (pintype "passive"))
      (node (ref "U8") (pin "13") (pinfunction "SMBDATA/NON_REM1_13") (pintype "passive"))
    )
    (net (code "58") (name "Net-(U8-SUSP_IND{slash}LOCAL_PWR{slash}(NON_REM0))") (class "Default")
      (node (ref "R105") (pin "2") (pinfunction "2_2") (pintype "passive"))
      (node (ref "U8") (pin "17") (pinfunction "SUSP_IND/LOCAL_PWR/(NON_REM0)_17") (pintype "passive"))
    )
    (net (code "59") (name "Net-(U8-USBDM_UP)") (class "Default")
      (node (ref "R108") (pin "1") (pinfunction "1_1") (pintype "passive"))
      (node (ref "U8") (pin "19") (pinfunction "USBDM_UP_19") (pintype "passive"))
    )
    (net (code "60") (name "Net-(U8-USBDP_UP)") (class "Default")
      (node (ref "R110") (pin "1") (pinfunction "1_1") (pintype "passive"))
      (node (ref "U8") (pin "20") (pinfunction "USBDP_UP_20") (pintype "passive"))
    )
    (net (code "61") (name "Net-(U8-VBUS_DET)") (class "Default")
      (node (ref "R100") (pin "1") (pinfunction "1_1") (pintype "passive"))
      (node (ref "R102") (pin "2") (pinfunction "2_2") (pintype "passive"))
      (node (ref "U8") (pin "16") (pinfunction "VBUS_DET_16") (pintype "passive"))
    )
    (net (code "62") (name "Net-(U8-XTALIN{slash}CLKIN)") (class "Default")
      (node (ref "C47") (pin "1") (pinfunction "1_1") (pintype "passive"))
      (node (ref "U8") (pin "22") (pinfunction "XTALIN/CLKIN_22") (pintype "passive"))
      (node (ref "X2") (pin "3") (pintype "passive"))
    )
    (net (code "63") (name "Net-(U8-XTALOUT{slash}(CLKIN_EN))") (class "Default")
      (node (ref "C46") (pin "1") (pinfunction "1_1") (pintype "passive"))
      (node (ref "U8") (pin "21") (pinfunction "XTALOUT/(CLKIN_EN)_21") (pintype "passive"))
      (node (ref "X2") (pin "1") (pintype "passive"))
    )
    (net (code "64") (name "Net-(U9-3V3OUT)") (class "Default")
      (node (ref "C41") (pin "1") (pinfunction "1_1") (pintype "passive"))
      (node (ref "C42") (pin "1") (pinfunction "1_1") (pintype "passive"))
      (node (ref "C43") (pin "1") (pinfunction "1_1") (pintype "passive"))
      (node (ref "C48") (pin "1") (pinfunction "1_1") (pintype "passive"))
      (node (ref "F5") (pin "2") (pinfunction "2_2") (pintype "passive"))
      (node (ref "R112") (pin "1") (pinfunction "1_1") (pintype "passive"))
      (node (ref "U9") (pin "10") (pinfunction "3V3OUT_10") (pintype "input"))
      (node (ref "U9") (pin "11") (pinfunction "~{RESET}_11") (pintype "input"))
      (node (ref "U9") (pin "12") (pinfunction "VCC_12") (pintype "power_in"))
    )
    (net (code "65") (name "Net-(U9-CBUS3)") (class "Default")
      (node (ref "R114") (pin "1") (pinfunction "1_1") (pintype "passive"))
      (node (ref "R115") (pin "1") (pinfunction "1_1") (pintype "passive"))
      (node (ref "U9") (pin "16") (pinfunction "CBUS3_16") (pintype "bidirectional"))
    )
    (net (code "66") (name "Net-(U9-VCCIO)") (class "Default")
      (node (ref "R111") (pin "2") (pinfunction "2_2") (pintype "passive"))
      (node (ref "R112") (pin "2") (pinfunction "2_2") (pintype "passive"))
      (node (ref "U9") (pin "20") (pinfunction "VCCIO_20") (pintype "power_in"))
    )
    (net (code "67") (name "Net-(U10-B1)") (class "Default")
      (node (ref "R119") (pin "1") (pinfunction "1_1") (pintype "passive"))
      (node (ref "U10") (pin "5") (pinfunction "B1_5") (pintype "passive"))
    )
    (net (code "68") (name "Net-(U10-B2)") (class "Default")
      (node (ref "R116") (pin "2") (pinfunction "2_2") (pintype "passive"))
      (node (ref "U10") (pin "2") (pinfunction "B2_2") (pintype "passive"))
    )
    (net (code "69") (name "Net-(U10-C1)") (class "Default")
      (node (ref "R118") (pin "1") (pinfunction "1_1") (pintype "passive"))
      (node (ref "U10") (pin "3") (pinfunction "C1_3") (pintype "passive"))
    )
    (net (code "70") (name "Net-(U10-C2)") (class "Default")
      (node (ref "R117") (pin "2") (pinfunction "2_2") (pintype "passive"))
      (node (ref "U10") (pin "6") (pinfunction "C2_6") (pintype "passive"))
    )
    (net (code "71") (name "VDD_IO") (class "Default")
      (node (ref "R111") (pin "1") (pinfunction "1_1") (pintype "passive"))
      (node (ref "R93") (pin "1") (pinfunction "1_1") (pintype "passive"))
      (node (ref "TP28") (pin "1") (pintype "passive"))
    )
    (net (code "72") (name "unconnected-(J14-Pad1)") (class "Default")
      (node (ref "J14") (pin "1") (pinfunction "1_1") (pintype "passive+no_connect"))
    )
    (net (code "73") (name "unconnected-(J14-Pad3)") (class "Default")
      (node (ref "J14") (pin "3") (pinfunction "3_3") (pintype "passive+no_connect"))
    )
    (net (code "74") (name "unconnected-(J14-Pad5)") (class "Default")
      (node (ref "J14") (pin "5") (pinfunction "5_5") (pintype "passive+no_connect"))
    )
    (net (code "75") (name "unconnected-(TP32-Pad1)") (class "Default")
      (node (ref "TP32") (pin "1") (pintype "passive+no_connect"))
    )
    (net (code "76") (name "unconnected-(TP33-Pad1)") (class "Default")
      (node (ref "TP33") (pin "1") (pintype "passive+no_connect"))
    )
    (net (code "77") (name "unconnected-(TP34-Pad1)") (class "Default")
      (node (ref "TP34") (pin "1") (pintype "passive+no_connect"))
    )
    (net (code "78") (name "unconnected-(TP35-Pad1)") (class "Default")
      (node (ref "TP35") (pin "1") (pintype "passive+no_connect"))
    )
    (net (code "79") (name "unconnected-(TP36-Pad1)") (class "Default")
      (node (ref "TP36") (pin "1") (pintype "passive+no_connect"))
    )
    (net (code "80") (name "unconnected-(TP37-Pad1)") (class "Default")
      (node (ref "TP37") (pin "1") (pintype "passive+no_connect"))
    )
    (net (code "81") (name "unconnected-(TP39-Pad1)") (class "Default")
      (node (ref "TP39") (pin "1") (pintype "passive+no_connect"))
    )
    (net (code "82") (name "unconnected-(TP40-Pad1)") (class "Default")
      (node (ref "TP40") (pin "1") (pintype "passive+no_connect"))
    )
    (net (code "83") (name "unconnected-(TP41-Pad1)") (class "Default")
      (node (ref "TP41") (pin "1") (pintype "passive+no_connect"))
    )
    (net (code "84") (name "unconnected-(TP43-Pad1)") (class "Default")
      (node (ref "TP43") (pin "1") (pintype "passive+no_connect"))
    )
    (net (code "85") (name "unconnected-(U7-CBUS0-Pad15)") (class "Default")
      (node (ref "U7") (pin "15") (pinfunction "CBUS0_15") (pintype "bidirectional+no_connect"))
    )
    (net (code "86") (name "unconnected-(U7-CBUS1-Pad14)") (class "Default")
      (node (ref "U7") (pin "14") (pinfunction "CBUS1_14") (pintype "bidirectional+no_connect"))
    )
    (net (code "87") (name "unconnected-(U7-CBUS2-Pad7)") (class "Default")
      (node (ref "U7") (pin "7") (pinfunction "CBUS2_7") (pintype "bidirectional+no_connect"))
    )
    (net (code "88") (name "unconnected-(U7-~{DCD}-Pad5)") (class "Default")
      (node (ref "U7") (pin "5") (pinfunction "~{DCD}_5") (pintype "input+no_connect"))
    )
    (net (code "89") (name "unconnected-(U7-~{RI}-Pad2)") (class "Default")
      (node (ref "U7") (pin "2") (pinfunction "~{RI}_2") (pintype "input+no_connect"))
    )
    (net (code "90") (name "unconnected-(U8-NC-Pad6)") (class "Default")
      (node (ref "U8") (pin "6") (pinfunction "NC_6") (pintype "passive+no_connect"))
    )
    (net (code "91") (name "unconnected-(U8-OCS1_N-Pad8)") (class "Default")
      (node (ref "U8") (pin "8") (pinfunction "OCS1_N_8") (pintype "passive+no_connect"))
    )
    (net (code "92") (name "unconnected-(U8-OCS2_N-Pad12)") (class "Default")
      (node (ref "U8") (pin "12") (pinfunction "OCS2_N_12") (pintype "passive+no_connect"))
    )
    (net (code "93") (name "unconnected-(U8-PLLFILT-Pad23)") (class "Default")
      (node (ref "U8") (pin "23") (pinfunction "PLLFILT_23") (pintype "passive+no_connect"))
    )
    (net (code "94") (name "unconnected-(U8-PRTPWR1{slash}(BC_EN1)-Pad7)") (class "Default")
      (node (ref "U8") (pin "7") (pinfunction "PRTPWR1/(BC_EN1)_7") (pintype "passive+no_connect"))
    )
    (net (code "95") (name "unconnected-(U8-PRTPWR2-Pad11)") (class "Default")
      (node (ref "U8") (pin "11") (pinfunction "PRTPWR2_11") (pintype "passive+no_connect"))
    )
    (net (code "96") (name "unconnected-(U9-CBUS0-Pad15)") (class "Default")
      (node (ref "U9") (pin "15") (pinfunction "CBUS0_15") (pintype "bidirectional+no_connect"))
    )
    (net (code "97") (name "unconnected-(U9-CBUS1-Pad14)") (class "Default")
      (node (ref "U9") (pin "14") (pinfunction "CBUS1_14") (pintype "bidirectional+no_connect"))
    )
    (net (code "98") (name "unconnected-(U9-CBUS2-Pad7)") (class "Default")
      (node (ref "U9") (pin "7") (pinfunction "CBUS2_7") (pintype "bidirectional+no_connect"))
    )
    (net (code "99") (name "unconnected-(U9-~{DCD}-Pad5)") (class "Default")
      (node (ref "U9") (pin "5") (pinfunction "~{DCD}_5") (pintype "input+no_connect"))
    )
    (net (code "100") (name "unconnected-(U9-~{RI}-Pad2)") (class "Default")
      (node (ref "U9") (pin "2") (pinfunction "~{RI}_2") (pintype "input+no_connect"))
    )
  )
)
